# hat.net
KiCad netlist of a schematic drawn in Altium Designer
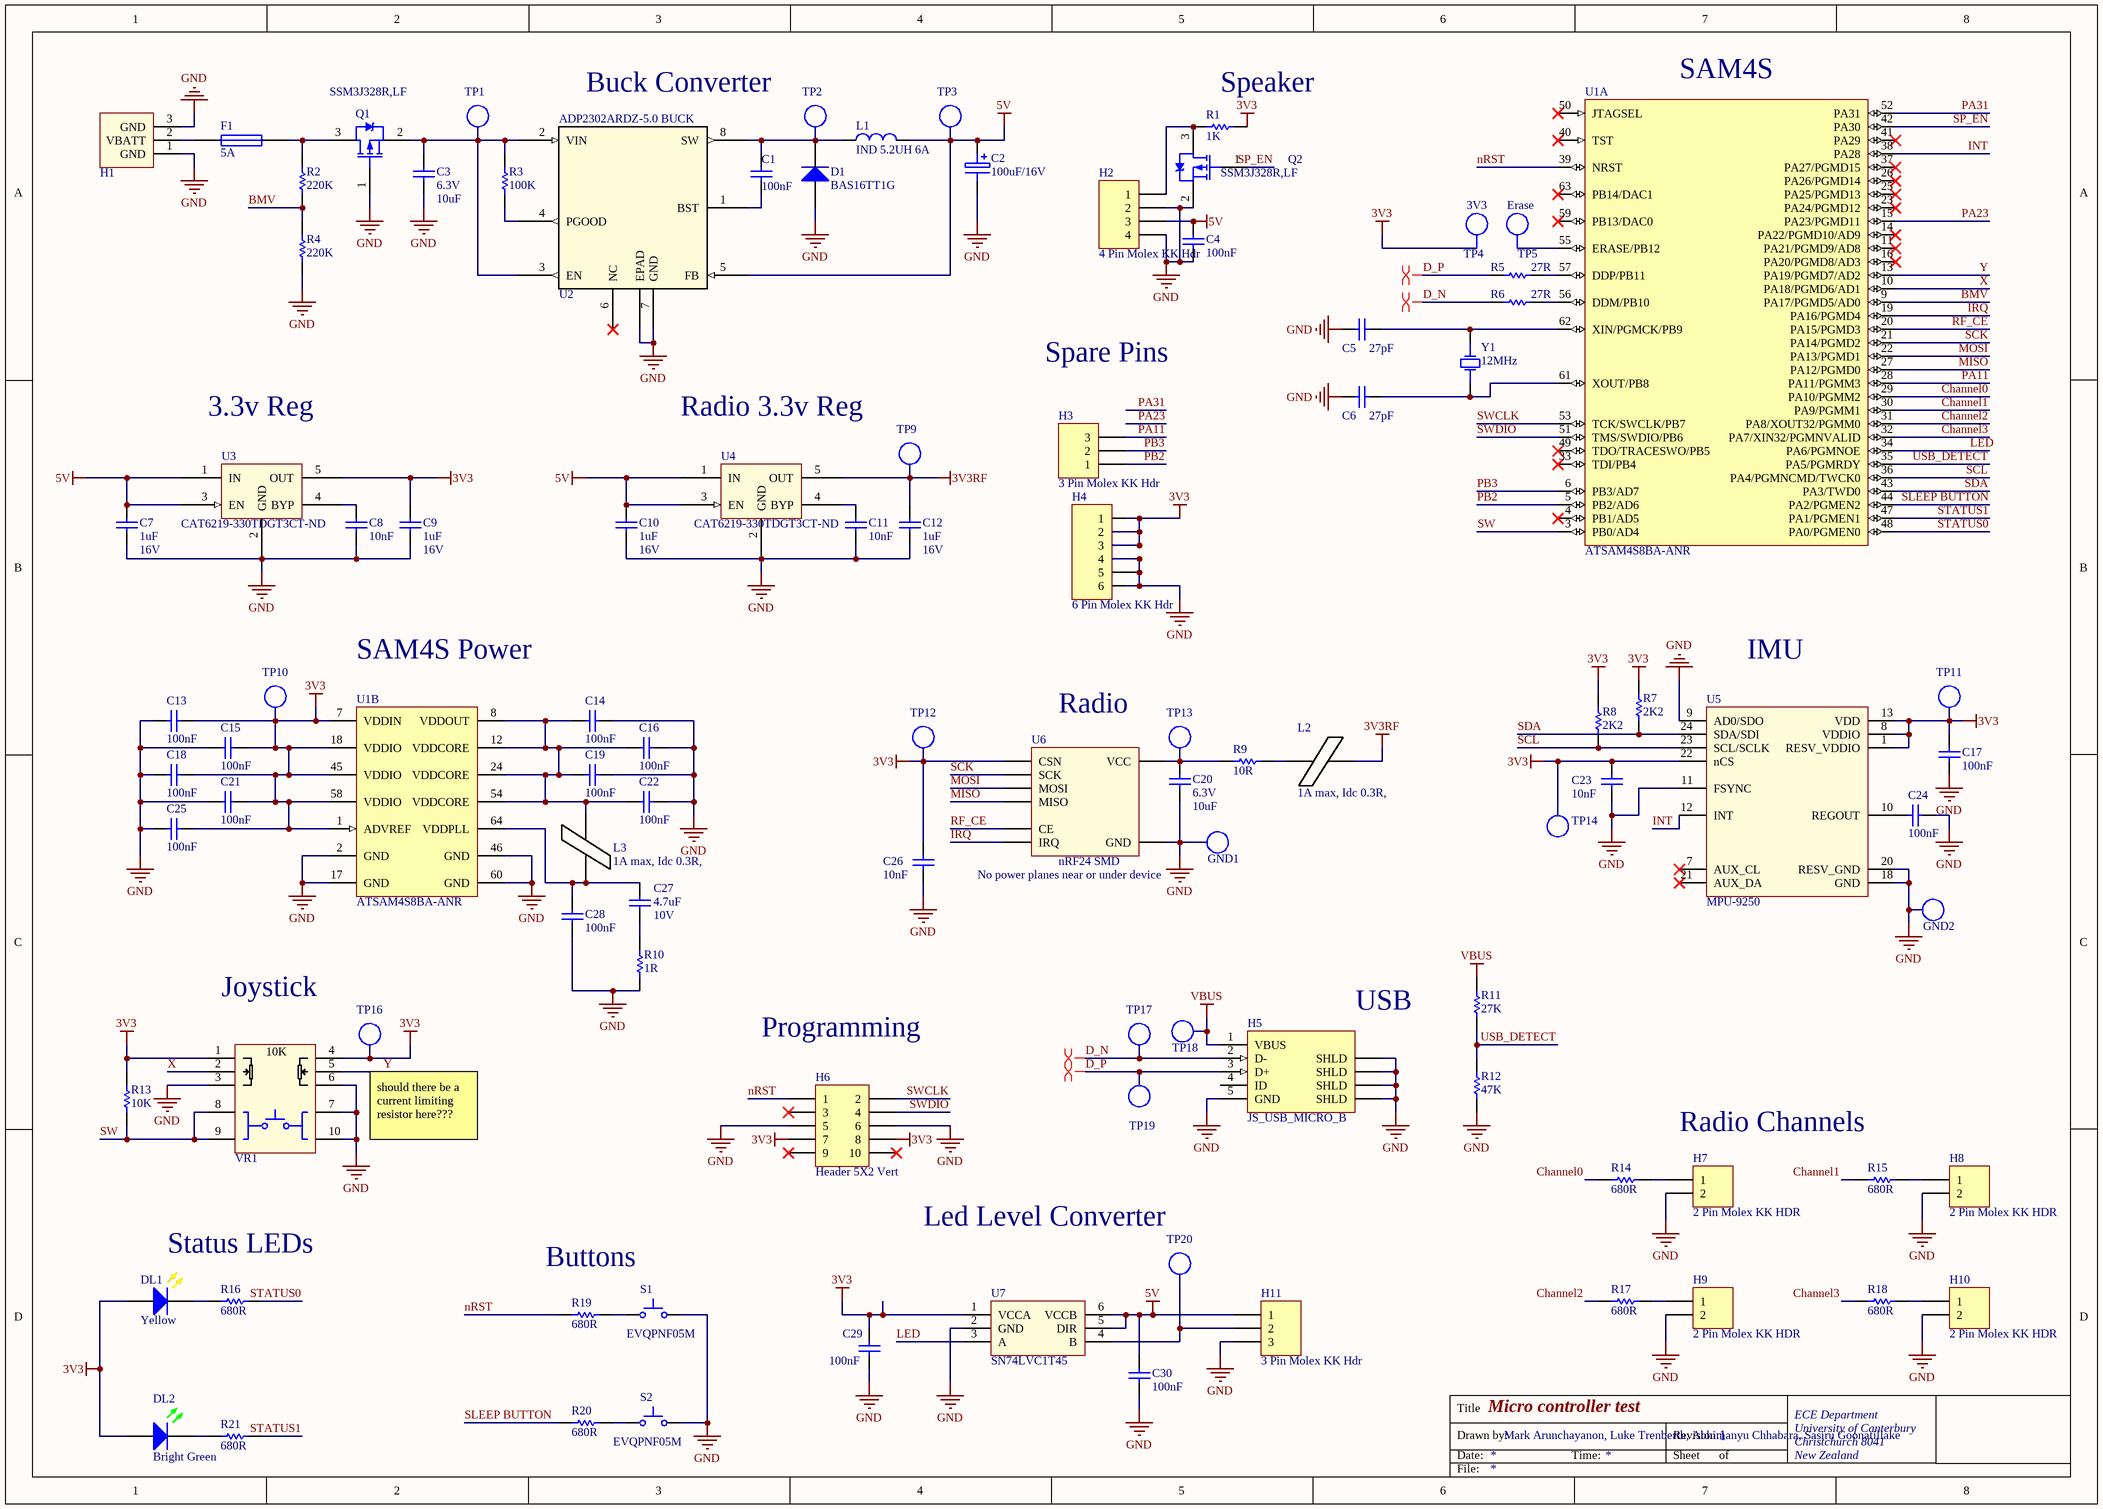
[diagram p0: hat.SchDoc]

(export (version "E")
  (design (tool "Eeschema 10.0.6"))
  (components
    (comp (ref "C1")
      (value "100nF")
      (footprint "CAPC1608L")
      (description "CAP CER 100nF X7R +-10% 50V 0603")
      (libsource (lib "ECE AD19Components_19V1") (part "CC_100nF_0603"))
    )
    (comp (ref "C2")
      (value "100uF/16V")
      (footprint "NICH-1")
      (description "CAP ALUM 100uF 16V SMD")
      (fields (field (name "MANUFACTURER") "Nichcon"))
      (libsource (lib "ECE AD19Components_19V1") (part "CA_100uF_16V"))
    )
    (comp (ref "C3")
      (value "10uF")
      (footprint "CAPC1608L")
      (description "CAP CER 10UF X5R +-20% 6V3 0603")
      (fields (field (name "VOLTAGE - RATED") "6.3V"))
      (libsource (lib "ECE AD19Components_19V1") (part "CC_10uF_0603"))
    )
    (comp (ref "C4")
      (value "100nF")
      (footprint "CAPC1608L")
      (description "CAP CER 100nF X7R +-10% 50V 0603")
      (libsource (lib "ECE AD19Components_19V1") (part "CC_100nF_0603"))
    )
    (comp (ref "C5")
      (value "27pF")
      (footprint "CAPC1608L")
      (description "CAP CER 27pF NPO/COG +-5% 50V 0603")
      (libsource (lib "ECE AD19Components_19V1") (part "CC_27pF_0603"))
    )
    (comp (ref "C6")
      (value "27pF")
      (footprint "CAPC1608L")
      (description "CAP CER 27pF NPO/COG +-5% 50V 0603")
      (libsource (lib "ECE AD19Components_19V1") (part "CC_27pF_0603"))
    )
    (comp (ref "C7")
      (value "1uF")
      (footprint "CAPC1608L")
      (description "CAP CER 1uF Y5V -20% +80% 16V 0603")
      (fields (field (name "MAX VOLTAGE") "16V"))
      (libsource (lib "ECE AD19Components_19V1") (part "CC_1uF_0603"))
    )
    (comp (ref "C8")
      (value "10nF")
      (footprint "CAPC1608L")
      (description "CAP CER 10nF X7R +-10% 50V 0603")
      (libsource (lib "ECE AD19Components_19V1") (part "CC_10nF_0603"))
    )
    (comp (ref "C9")
      (value "1uF")
      (footprint "CAPC1608L")
      (description "CAP CER 1uF Y5V -20% +80% 16V 0603")
      (fields (field (name "MAX VOLTAGE") "16V"))
      (libsource (lib "ECE AD19Components_19V1") (part "CC_1uF_0603"))
    )
    (comp (ref "C10")
      (value "1uF")
      (footprint "CAPC1608L")
      (description "CAP CER 1uF Y5V -20% +80% 16V 0603")
      (fields (field (name "MAX VOLTAGE") "16V"))
      (libsource (lib "ECE AD19Components_19V1") (part "CC_1uF_0603"))
    )
    (comp (ref "C11")
      (value "10nF")
      (footprint "CAPC1608L")
      (description "CAP CER 10nF X7R +-10% 50V 0603")
      (libsource (lib "ECE AD19Components_19V1") (part "CC_10nF_0603"))
    )
    (comp (ref "C12")
      (value "1uF")
      (footprint "CAPC1608L")
      (description "CAP CER 1uF Y5V -20% +80% 16V 0603")
      (fields (field (name "MAX VOLTAGE") "16V"))
      (libsource (lib "ECE AD19Components_19V1") (part "CC_1uF_0603"))
    )
    (comp (ref "C13")
      (value "100nF")
      (footprint "CAPC1608L")
      (description "CAP CER 100nF X7R +-10% 50V 0603")
      (libsource (lib "ECE AD19Components_19V1") (part "CC_100nF_0603"))
    )
    (comp (ref "C14")
      (value "100nF")
      (footprint "CAPC1608L")
      (description "CAP CER 100nF X7R +-10% 50V 0603")
      (libsource (lib "ECE AD19Components_19V1") (part "CC_100nF_0603"))
    )
    (comp (ref "C15")
      (value "100nF")
      (footprint "CAPC1608L")
      (description "CAP CER 100nF X7R +-10% 50V 0603")
      (libsource (lib "ECE AD19Components_19V1") (part "CC_100nF_0603"))
    )
    (comp (ref "C16")
      (value "100nF")
      (footprint "CAPC1608L")
      (description "CAP CER 100nF X7R +-10% 50V 0603")
      (libsource (lib "ECE AD19Components_19V1") (part "CC_100nF_0603"))
    )
    (comp (ref "C17")
      (value "100nF")
      (footprint "CAPC1608L")
      (description "CAP CER 100nF X7R +-10% 50V 0603")
      (libsource (lib "ECE AD19Components_19V1") (part "CC_100nF_0603"))
    )
    (comp (ref "C18")
      (value "100nF")
      (footprint "CAPC1608L")
      (description "CAP CER 100nF X7R +-10% 50V 0603")
      (libsource (lib "ECE AD19Components_19V1") (part "CC_100nF_0603"))
    )
    (comp (ref "C19")
      (value "100nF")
      (footprint "CAPC1608L")
      (description "CAP CER 100nF X7R +-10% 50V 0603")
      (libsource (lib "ECE AD19Components_19V1") (part "CC_100nF_0603"))
    )
    (comp (ref "C20")
      (value "10uF")
      (footprint "CAPC1608L")
      (description "CAP CER 10UF X5R +-20% 6V3 0603")
      (fields (field (name "VOLTAGE - RATED") "6.3V"))
      (libsource (lib "ECE AD19Components_19V1") (part "CC_10uF_0603"))
    )
    (comp (ref "C21")
      (value "100nF")
      (footprint "CAPC1608L")
      (description "CAP CER 100nF X7R +-10% 50V 0603")
      (libsource (lib "ECE AD19Components_19V1") (part "CC_100nF_0603"))
    )
    (comp (ref "C22")
      (value "100nF")
      (footprint "CAPC1608L")
      (description "CAP CER 100nF X7R +-10% 50V 0603")
      (libsource (lib "ECE AD19Components_19V1") (part "CC_100nF_0603"))
    )
    (comp (ref "C23")
      (value "10nF")
      (footprint "CAPC1608L")
      (description "CAP CER 10nF X7R +-10% 50V 0603")
      (libsource (lib "ECE AD19Components_19V1") (part "CC_10nF_0603"))
    )
    (comp (ref "C24")
      (value "100nF")
      (footprint "CAPC1608L")
      (description "CAP CER 100nF X7R +-10% 50V 0603")
      (libsource (lib "ECE AD19Components_19V1") (part "CC_100nF_0603"))
    )
    (comp (ref "C25")
      (value "100nF")
      (footprint "CAPC1608L")
      (description "CAP CER 100nF X7R +-10% 50V 0603")
      (libsource (lib "ECE AD19Components_19V1") (part "CC_100nF_0603"))
    )
    (comp (ref "C26")
      (value "10nF")
      (footprint "CAPC1608L")
      (description "CAP CER 10nF X7R +-10% 50V 0603")
      (libsource (lib "ECE AD19Components_19V1") (part "CC_10nF_0603"))
    )
    (comp (ref "C27")
      (value "4.7uF")
      (footprint "CAPC1608N")
      (description "CAP CER 4.7uF X5R +-20%  10V 0603")
      (fields (field (name "MAX VOLTAGE") "10V"))
      (libsource (lib "ECE AD19Components_19V1") (part "CC_4.7uF_0603"))
    )
    (comp (ref "C28")
      (value "100nF")
      (footprint "CAPC1608L")
      (description "CAP CER 100nF X7R +-10% 50V 0603")
      (libsource (lib "ECE AD19Components_19V1") (part "CC_100nF_0603"))
    )
    (comp (ref "C29")
      (value "100nF")
      (footprint "CAPC1608L")
      (description "CAP CER 100nF X7R +-10% 50V 0603")
      (libsource (lib "ECE AD19Components_19V1") (part "CC_100nF_0603"))
    )
    (comp (ref "C30")
      (value "100nF")
      (footprint "CAPC1608L")
      (description "CAP CER 100nF X7R +-10% 50V 0603")
      (libsource (lib "ECE AD19Components_19V1") (part "CC_100nF_0603"))
    )
    (comp (ref "D1")
      (value "BAS16TT1G")
      (footprint "SOT416")
      (description "Diode Switching, Vr 75V, 200mA, SOT-416")
      (fields (field (name "MANUFACTURER") "ON Semiconductor"))
      (libsource (lib "ECE AD19Components_19V1") (part "DR_BAS16TT1G"))
    )
    (comp (ref "DL1")
      (value "Yellow")
      (footprint "WL-SMCW0603")
      (description "LED Yellow 120mcd 0603 SMD")
      (fields
        (field (name "MANUFACTURER") "WURTH ELEKTRONIK")
        (field (name "MANUFACTURER PART NUMBER") "150060YS75000")
        (field (name "LED COLOUR") "Yellow")
      )
      (libsource (lib "ECE AD19Components_19V1") (part "DL_150060YS75000"))
    )
    (comp (ref "DL2")
      (value "Bright Green")
      (footprint "WL-SMCW0603")
      (description "LED Bright Green 40mcd 0603 SMD")
      (fields
        (field (name "MANUFACTURER") "WURTH ELEKTRONIK")
        (field (name "MANUFACTURER PART NUMBER") "150060VS75000")
        (field (name "LED COLOUR") "Bright Green")
      )
      (libsource (lib "ECE AD19Components_19V1") (part "DL_150060VS75000"))
    )
    (comp (ref "F1")
      (value "5A")
      (footprint "RESC3216N")
      (description "Fuse 5.0A Fast Acting 1206 SMD")
      (fields (field (name "MANUFACTURER PART NUMBER") "C1F5") (field (name "MANUFACTURER") "Bel TRP"))
      (libsource (lib "ECE AD19Components_19V1") (part "FS_Fuse_5.0A"))
    )
    (comp (ref "GND1")
      (value "TP_0603")
      (footprint "TP_0603")
      (description "Test Point 1.65X0.9X1.2mm SMD")
      (fields
        (field (name "MANUFACTURER") "TE Connectivity AMP Connectors")
        (field (name "MANUFACTURER PART NUMBER") "1625854-3")
      )
      (libsource (lib "ECE AD19Components_19V1") (part "TP_0603"))
    )
    (comp (ref "GND2")
      (value "TP_0603")
      (footprint "TP_0603")
      (description "Test Point 1.65X0.9X1.2mm SMD")
      (fields
        (field (name "MANUFACTURER") "TE Connectivity AMP Connectors")
        (field (name "MANUFACTURER PART NUMBER") "1625854-3")
      )
      (libsource (lib "ECE AD19Components_19V1") (part "TP_0603"))
    )
    (comp (ref "H1")
      (value "Battery_HEADER_3pin")
      (footprint "BATT_HEADER_3POS")
      (description "3Pin Header 2.54mm spacing")
      (libsource (lib "ENCE461AD19_19V2") (part "Battery_HEADER_3pin"))
    )
    (comp (ref "H2")
      (value "4 Pin Molex KK Hdr")
      (footprint "MOLEX_KK_4_HDR")
      (description "CONN HEADER 4POS 2.54mm VERT_Thru Hole")
      (fields (field (name "MANUFACTURER") "Molex") (field (name "Comment") "SMD Vert 1.25mm"))
      (libsource (lib "ECE AD19Components_19V1") (part "JA_MOLEX_KK_4POS"))
    )
    (comp (ref "H3")
      (value "3 Pin Molex KK Hdr")
      (footprint "MOLEX_KK_3_HDR")
      (description "CONN HEADER 3POS 2.54mm VERT_Thru Hole")
      (fields (field (name "MANUFACTURER") "Molex"))
      (libsource (lib "") (part "JA_MOLEX_KK_3POS_1"))
    )
    (comp (ref "H4")
      (value "6 Pin Molex KK Hdr")
      (footprint "MOLEX_KK_6_HDR")
      (description "CONN HEADER 6POS 2.54mm VERT_Thru Hole")
      (fields (field (name "Comment") "SMD Vert 1.25mm"))
      (libsource (lib "ECE AD19Components_19V1") (part "JA_MOLEX_KK_6POS"))
    )
    (comp (ref "H5")
      (value "JS_USB_MICRO_B")
      (footprint "FCI_USB_10118194-0001LF")
      (description "CONN USB MICRO B RECPT SMT R/A")
      (fields (field (name "MANUFACTURER") "FCI") (field (name "MANUFACTURER PART NUMBER") "10118194-0001LF"))
      (libsource (lib "ECE AD19Components_19V1") (part "JS_USB_MICRO_B_SMT"))
    )
    (comp (ref "H6")
      (value "Header 5X2 Vert")
      (footprint "IDC2.54-V10D")
      (description "IDC Header, 2,54mm, 10-Pin, Vert")
      (libsource (lib "ECE AD19Components_19V1") (part "JA_HDR_IDC_5X2_VERT"))
    )
    (comp (ref "H7")
      (value "2 Pin Molex KK HDR")
      (footprint "MOLEX_KK_2_HDR")
      (description "CONN HEADER 2POS 2.54mm VERT_Thru Hole")
      (fields (field (name "Comment") "SMD Vert 1.25mm"))
      (libsource (lib "ECE AD19Components_19V1") (part "JA_MOLEX_KK_2POS"))
    )
    (comp (ref "H8")
      (value "2 Pin Molex KK HDR")
      (footprint "MOLEX_KK_2_HDR")
      (description "CONN HEADER 2POS 2.54mm VERT_Thru Hole")
      (fields (field (name "Comment") "SMD Vert 1.25mm"))
      (libsource (lib "ECE AD19Components_19V1") (part "JA_MOLEX_KK_2POS"))
    )
    (comp (ref "H9")
      (value "2 Pin Molex KK HDR")
      (footprint "MOLEX_KK_2_HDR")
      (description "CONN HEADER 2POS 2.54mm VERT_Thru Hole")
      (fields (field (name "Comment") "SMD Vert 1.25mm"))
      (libsource (lib "ECE AD19Components_19V1") (part "JA_MOLEX_KK_2POS"))
    )
    (comp (ref "H10")
      (value "2 Pin Molex KK HDR")
      (footprint "MOLEX_KK_2_HDR")
      (description "CONN HEADER 2POS 2.54mm VERT_Thru Hole")
      (fields (field (name "Comment") "SMD Vert 1.25mm"))
      (libsource (lib "ECE AD19Components_19V1") (part "JA_MOLEX_KK_2POS"))
    )
    (comp (ref "H11")
      (value "3 Pin Molex KK Hdr")
      (footprint "MOLEX_KK_3_HDR")
      (description "CONN HEADER 3POS 2.54mm VERT_Thru Hole")
      (fields (field (name "MANUFACTURER") "Molex") (field (name "Comment") "SMD Vert 1.25mm"))
      (libsource (lib "ECE AD19Components_19V1") (part "JA_MOLEX_KK_3POS"))
    )
    (comp (ref "L1")
      (value "IND 5.2UH 6A")
      (footprint "INDUCTOR5u2")
      (description "FIXED IND 5.2UH 6A 22 MOHM SMD")
      (fields
        (field (name "MANUFACTURER") "Sumida America Components Inc.")
        (field (name "MANUFACTURER PART NUMBER") "CDRH104RNP-5R2NC")
      )
      (libsource (lib "ENCE461AD19_19V2") (part "CDRH104RNP-5R2NC"))
    )
    (comp (ref "L2")
      (value "1A max, Idc 0.3R,")
      (footprint "INDC3216L")
      (description "Ferrite Bead, Rdc 0.3R, Z100MHZ 600R, Imax 1A, SMD 1206")
      (fields
        (field (name "MANUFACTURER") "FAIR-RITE")
        (field (name "MANUFACTURER PART NUMBER") "2512066017Y1")
      )
      (libsource (lib "ECE AD19Components_19V1") (part "IN_Ferrite-Bead"))
    )
    (comp (ref "L3")
      (value "1A max, Idc 0.3R,")
      (footprint "INDC3216L")
      (description "Ferrite Bead, Rdc 0.3R, Z100MHZ 600R, Imax 1A, SMD 1206")
      (fields
        (field (name "MANUFACTURER") "FAIR-RITE")
        (field (name "MANUFACTURER PART NUMBER") "2512066017Y1")
      )
      (libsource (lib "ECE AD19Components_19V1") (part "IN_Ferrite-Bead"))
    )
    (comp (ref "Q1")
      (value "SSM3J328R,LF")
      (footprint "SOT23_L")
      (description "MOSFET P-CH 20V 6A SOT23-3")
      (fields
        (field (name "MANUFACTURER") "Toshiba")
        (field (name "MANUFACTURER PART NUMBER") "SSM3J328R,LF")
      )
      (libsource (lib "ECE AD19Components_19V1") (part "TM_SSM3J328R"))
    )
    (comp (ref "Q2")
      (value "SSM3J328R,LF")
      (footprint "SOT23_L")
      (description "MOSFET P-CH 20V 6A SOT23-3")
      (fields
        (field (name "MANUFACTURER") "Toshiba")
        (field (name "MANUFACTURER PART NUMBER") "SSM3J328R,LF")
      )
      (libsource (lib "ECE AD19Components_19V1") (part "TM_SSM3J328R"))
    )
    (comp (ref "R1")
      (value "1K")
      (footprint "RESC1608L")
      (description "RES 1.0K OHM 1/10W 5% 0603 SMD")
      (libsource (lib "ECE AD19Components_19V1") (part "RS_1K"))
    )
    (comp (ref "R2")
      (value "220K")
      (footprint "RESC1608L")
      (description "RES 3.3K OHM 1/10W 5% 0603 SMD")
      (libsource (lib "ECE AD19Components_19V1") (part "RS_220K"))
    )
    (comp (ref "R3")
      (value "100K")
      (footprint "RESC1608L")
      (description "RES 100K OHM 1/10W 5% 0603 SMD")
      (libsource (lib "ECE AD19Components_19V1") (part "RS_100K"))
    )
    (comp (ref "R4")
      (value "220K")
      (footprint "RESC1608L")
      (description "RES 3.3K OHM 1/10W 5% 0603 SMD")
      (libsource (lib "ECE AD19Components_19V1") (part "RS_220K"))
    )
    (comp (ref "R5")
      (value "27R")
      (footprint "RESC3216L")
      (description "RES 27R OHM 1/4W 5% 1206 SMD")
      (libsource (lib "ECE AD19Components_19V1") (part "RT_27R"))
    )
    (comp (ref "R6")
      (value "27R")
      (footprint "RESC3216L")
      (description "RES 27R OHM 1/4W 5% 1206 SMD")
      (libsource (lib "ECE AD19Components_19V1") (part "RT_27R"))
    )
    (comp (ref "R7")
      (value "2K2")
      (footprint "RESC1608L")
      (description "RES 2.2K OHM 1/10W 5% 0603 SMD")
      (libsource (lib "ECE AD19Components_19V1") (part "RS_2K2"))
    )
    (comp (ref "R8")
      (value "2K2")
      (footprint "RESC1608L")
      (description "RES 2.2K OHM 1/10W 5% 0603 SMD")
      (libsource (lib "ECE AD19Components_19V1") (part "RS_2K2"))
    )
    (comp (ref "R9")
      (value "10R")
      (footprint "RESC1608L")
      (description "RES 10 OHM 1/10W 5% 0603 SMD")
      (libsource (lib "ECE AD19Components_19V1") (part "RS_10R"))
    )
    (comp (ref "R10")
      (value "1R")
      (footprint "RESC3216L")
      (description "RES 1R OHM 1/4W 5% 1206 SMD")
      (libsource (lib "ECE AD19Components_19V1") (part "RT_1R"))
    )
    (comp (ref "R11")
      (value "27K")
      (footprint "RESC1608L")
      (description "RES 27K OHM 1/10W 5% 0603 SMD")
      (libsource (lib "ECE AD19Components_19V1") (part "RS_27K"))
    )
    (comp (ref "R12")
      (value "47K")
      (footprint "RESC1608N")
      (description "RES 47.0K OHM 1/10W 5% 0603 SMD")
      (libsource (lib "ECE AD19Components_19V1") (part "RS_47K"))
    )
    (comp (ref "R13")
      (value "10K")
      (footprint "RESC1608L")
      (description "RES 10.0K OHM 1/10W 5% 0603 SMD")
      (libsource (lib "ECE AD19Components_19V1") (part "RS_10K"))
    )
    (comp (ref "R14")
      (value "680R")
      (footprint "RESC1608L")
      (description "RES 680 OHM 1/10W 5% 0603 SMD")
      (libsource (lib "ECE AD19Components_19V1") (part "RS_680R"))
    )
    (comp (ref "R15")
      (value "680R")
      (footprint "RESC1608L")
      (description "RES 680 OHM 1/10W 5% 0603 SMD")
      (libsource (lib "ECE AD19Components_19V1") (part "RS_680R"))
    )
    (comp (ref "R16")
      (value "680R")
      (footprint "RESC1608L")
      (description "RES 680 OHM 1/10W 5% 0603 SMD")
      (libsource (lib "ECE AD19Components_19V1") (part "RS_680R"))
    )
    (comp (ref "R17")
      (value "680R")
      (footprint "RESC1608L")
      (description "RES 680 OHM 1/10W 5% 0603 SMD")
      (libsource (lib "ECE AD19Components_19V1") (part "RS_680R"))
    )
    (comp (ref "R18")
      (value "680R")
      (footprint "RESC1608L")
      (description "RES 680 OHM 1/10W 5% 0603 SMD")
      (libsource (lib "ECE AD19Components_19V1") (part "RS_680R"))
    )
    (comp (ref "R19")
      (value "680R")
      (footprint "RESC1608L")
      (description "RES 680 OHM 1/10W 5% 0603 SMD")
      (libsource (lib "ECE AD19Components_19V1") (part "RS_680R"))
    )
    (comp (ref "R20")
      (value "680R")
      (footprint "RESC1608L")
      (description "RES 680 OHM 1/10W 5% 0603 SMD")
      (libsource (lib "ECE AD19Components_19V1") (part "RS_680R"))
    )
    (comp (ref "R21")
      (value "680R")
      (footprint "RESC1608L")
      (description "RES 680 OHM 1/10W 5% 0603 SMD")
      (libsource (lib "ECE AD19Components_19V1") (part "RS_680R"))
    )
    (comp (ref "S1")
      (value "EVQPNF05M")
      (footprint "EVQPNF05M")
      (description "Panasonic 6 x 3.5mm SMD Light Touch Switch Type SMD")
      (fields (field (name "MANUFACTURER") "Panasonic"))
      (libsource (lib "ECE AD19Components_19V1") (part "WS_EVQPNF05M"))
    )
    (comp (ref "S2")
      (value "EVQPNF05M")
      (footprint "EVQPNF05M")
      (description "Panasonic 6 x 3.5mm SMD Light Touch Switch Type SMD")
      (fields (field (name "MANUFACTURER") "Panasonic"))
      (libsource (lib "ECE AD19Components_19V1") (part "WS_EVQPNF05M"))
    )
    (comp (ref "TP1")
      (value "TP_0603")
      (footprint "TP_0603")
      (description "Test Point 1.65X0.9X1.2mm SMD")
      (fields
        (field (name "MANUFACTURER") "TE Connectivity AMP Connectors")
        (field (name "MANUFACTURER PART NUMBER") "1625854-3")
      )
      (libsource (lib "ECE AD19Components_19V1") (part "TP_0603"))
    )
    (comp (ref "TP2")
      (value "TP_0603")
      (footprint "TP_0603")
      (description "Test Point 1.65X0.9X1.2mm SMD")
      (fields
        (field (name "MANUFACTURER") "TE Connectivity AMP Connectors")
        (field (name "MANUFACTURER PART NUMBER") "1625854-3")
      )
      (libsource (lib "ECE AD19Components_19V1") (part "TP_0603"))
    )
    (comp (ref "TP3")
      (value "TP_0603")
      (footprint "TP_0603")
      (description "Test Point 1.65X0.9X1.2mm SMD")
      (fields
        (field (name "MANUFACTURER") "TE Connectivity AMP Connectors")
        (field (name "MANUFACTURER PART NUMBER") "1625854-3")
      )
      (libsource (lib "ECE AD19Components_19V1") (part "TP_0603"))
    )
    (comp (ref "TP4")
      (value "3V3")
      (footprint "TP_1206")
      (description "Test-Point 3.3x1.6x2.1mm SMD")
      (fields
        (field (name "MANUFACTURER") "Harwin Inc")
        (field (name "MANUFACTURER PART NUMBER") "S1751-46R")
      )
      (libsource (lib "ECE AD19Components_19V1") (part "TP_1206"))
    )
    (comp (ref "TP5")
      (value "Erase")
      (footprint "TP_1206")
      (description "Test-Point 3.3x1.6x2.1mm SMD")
      (fields
        (field (name "MANUFACTURER") "Harwin Inc")
        (field (name "MANUFACTURER PART NUMBER") "S1751-46R")
      )
      (libsource (lib "ECE AD19Components_19V1") (part "TP_1206"))
    )
    (comp (ref "TP9")
      (value "TP_0603")
      (footprint "TP_0603")
      (description "Test Point 1.65X0.9X1.2mm SMD")
      (fields
        (field (name "MANUFACTURER") "TE Connectivity AMP Connectors")
        (field (name "MANUFACTURER PART NUMBER") "1625854-3")
      )
      (libsource (lib "ECE AD19Components_19V1") (part "TP_0603"))
    )
    (comp (ref "TP10")
      (value "TP_0603")
      (footprint "TP_0603")
      (description "Test Point 1.65X0.9X1.2mm SMD")
      (fields
        (field (name "MANUFACTURER") "TE Connectivity AMP Connectors")
        (field (name "MANUFACTURER PART NUMBER") "1625854-3")
      )
      (libsource (lib "ECE AD19Components_19V1") (part "TP_0603"))
    )
    (comp (ref "TP11")
      (value "TP_0603")
      (footprint "TP_0603")
      (description "Test Point 1.65X0.9X1.2mm SMD")
      (fields
        (field (name "MANUFACTURER") "TE Connectivity AMP Connectors")
        (field (name "MANUFACTURER PART NUMBER") "1625854-3")
      )
      (libsource (lib "ECE AD19Components_19V1") (part "TP_0603"))
    )
    (comp (ref "TP12")
      (value "TP_0603")
      (footprint "TP_0603")
      (description "Test Point 1.65X0.9X1.2mm SMD")
      (fields
        (field (name "MANUFACTURER") "TE Connectivity AMP Connectors")
        (field (name "MANUFACTURER PART NUMBER") "1625854-3")
      )
      (libsource (lib "ECE AD19Components_19V1") (part "TP_0603"))
    )
    (comp (ref "TP13")
      (value "TP_0603")
      (footprint "TP_0603")
      (description "Test Point 1.65X0.9X1.2mm SMD")
      (fields
        (field (name "MANUFACTURER") "TE Connectivity AMP Connectors")
        (field (name "MANUFACTURER PART NUMBER") "1625854-3")
      )
      (libsource (lib "ECE AD19Components_19V1") (part "TP_0603"))
    )
    (comp (ref "TP14")
      (value "TP_0603")
      (footprint "TP_0603")
      (description "Test Point 1.65X0.9X1.2mm SMD")
      (fields
        (field (name "MANUFACTURER") "TE Connectivity AMP Connectors")
        (field (name "MANUFACTURER PART NUMBER") "1625854-3")
      )
      (libsource (lib "ECE AD19Components_19V1") (part "TP_0603"))
    )
    (comp (ref "TP16")
      (value "TP_0603")
      (footprint "TP_0603")
      (description "Test Point 1.65X0.9X1.2mm SMD")
      (fields
        (field (name "MANUFACTURER") "TE Connectivity AMP Connectors")
        (field (name "MANUFACTURER PART NUMBER") "1625854-3")
      )
      (libsource (lib "ECE AD19Components_19V1") (part "TP_0603"))
    )
    (comp (ref "TP17")
      (value "TP_0603")
      (footprint "TP_0603")
      (description "Test Point 1.65X0.9X1.2mm SMD")
      (fields
        (field (name "MANUFACTURER") "TE Connectivity AMP Connectors")
        (field (name "MANUFACTURER PART NUMBER") "1625854-3")
      )
      (libsource (lib "ECE AD19Components_19V1") (part "TP_0603"))
    )
    (comp (ref "TP18")
      (value "TP_0603")
      (footprint "TP_0603")
      (description "Test Point 1.65X0.9X1.2mm SMD")
      (fields
        (field (name "MANUFACTURER") "TE Connectivity AMP Connectors")
        (field (name "MANUFACTURER PART NUMBER") "1625854-3")
      )
      (libsource (lib "ECE AD19Components_19V1") (part "TP_0603"))
    )
    (comp (ref "TP19")
      (value "TP_0603")
      (footprint "TP_0603")
      (description "Test Point 1.65X0.9X1.2mm SMD")
      (fields
        (field (name "MANUFACTURER") "TE Connectivity AMP Connectors")
        (field (name "MANUFACTURER PART NUMBER") "1625854-3")
      )
      (libsource (lib "ECE AD19Components_19V1") (part "TP_0603"))
    )
    (comp (ref "TP20")
      (value "TP_0603")
      (footprint "TP_0603")
      (description "Test Point 1.65X0.9X1.2mm SMD")
      (fields
        (field (name "MANUFACTURER") "TE Connectivity AMP Connectors")
        (field (name "MANUFACTURER PART NUMBER") "1625854-3")
      )
      (libsource (lib "ECE AD19Components_19V1") (part "TP_0603"))
    )
    (comp (ref "U1")
      (value "ATSAM4S8BA-ANR")
      (footprint "LQFP64_L")
      (description "IC MCU 32BIT 512KB FLASH 64LQFP")
      (fields (field (name "MANUFACTURER") "Atmel"))
      (libsource (lib "ECE AD19Components_19V1") (part "SE_ATSAM4S16BA-MU"))
    )
    (comp (ref "U2")
      (value "ADP2302ARDZ-5.0 BUCK")
      (footprint "RD_8_1")
      (description "IC REG BUCK 5V 2A 8SOIC")
      (fields (field (name "MANUFACTURER_PART_NUMBER") "ADP2302ARDZ-5.0-R7"))
      (libsource (lib "ENCE461AD19_19V2") (part "ADP2302ARDZ-5.0-R7"))
    )
    (comp (ref "U3")
      (value "CAT6219-330TDGT3")
      (footprint "SOT95P280X145-5N")
      (description "IC REG LIN 3.3V 500MA TSOT23-5")
      (fields
        (field (name "BASE PART NUMBER") "CAT6219")
        (field (name "SUPPLIER PART NUMBER") "CAT6219-330TDGT3CT-ND")
      )
      (libsource (lib "ENCE461AD19_19V2") (part "SV_CAT6219-330TDGT3"))
    )
    (comp (ref "U4")
      (value "CAT6219-330TDGT3")
      (footprint "SOT95P280X145-5N")
      (description "IC REG LIN 3.3V 500MA TSOT23-5")
      (fields
        (field (name "BASE PART NUMBER") "CAT6219")
        (field (name "SUPPLIER PART NUMBER") "CAT6219-330TDGT3CT-ND")
      )
      (libsource (lib "ENCE461AD19_19V2") (part "SV_CAT6219-330TDGT3"))
    )
    (comp (ref "U5")
      (value "MPU-9250")
      (footprint "Quad24")
      (description "9 axis IMU")
      (libsource (lib "ENCE461AD19_19V2") (part "MPU-9250"))
    )
    (comp (ref "U6")
      (value "nRF24 SMD")
      (footprint "NRF24")
      (description "nRF24 SMD Module")
      (fields (field (name "WARNING") "No power planes near or under device"))
      (libsource (lib "ENCE461AD19_19V2") (part "NRF24"))
    )
    (comp (ref "U7")
      (value "SN74LVC1T45")
      (footprint "SOT23-6_N")
      (description "1.8V - 5V level converter")
      (libsource (lib "ENCE461_extras_2020") (part "SN74LVC1T45"))
    )
    (comp (ref "VR1")
      (value "Joystick 10k with Sw")
      (footprint "Joystick_Sw")
      (description "JOYSTICK 10K OHM 2 AXIS TH")
      (libsource (lib "ENCE461AD19_19V2") (part "Joystick 10k with Sw"))
    )
    (comp (ref "Y1")
      (value "12MHz")
      (footprint "6.0X3.5-4")
      (description "CRYSTAL 12MHZ 18PF 6X3.5mm SMD")
      (fields
        (field (name "MANUFACTURER") "CTS-Frequency Controls")
        (field (name "MANUFACTURER PART NUMBER") "406C35D12M00000")
        (field (name "FREQUENCY") "12MHz")
      )
      (libsource (lib "ECE AD19Components_19V1") (part "XT_CRYSTAL_12MHz_18pF"))
    )
  )
  (nets
    (net (code "1") (name "/BMV") (class "Default")
      (node (ref "R2") (pin "1") (pinfunction "1_1") (pintype "passive"))
      (node (ref "R4") (pin "2") (pinfunction "2_2") (pintype "passive"))
      (node (ref "U1") (pin "9") (pinfunction "PA17/PGMD5/AD0_9") (pintype "bidirectional"))
    )
    (net (code "2") (name "/Channel0") (class "Default")
      (node (ref "R14") (pin "1") (pinfunction "1_1") (pintype "passive"))
      (node (ref "U1") (pin "29") (pinfunction "PA10/PGMM2_29") (pintype "bidirectional"))
    )
    (net (code "3") (name "/Channel1") (class "Default")
      (node (ref "R15") (pin "1") (pinfunction "1_1") (pintype "passive"))
      (node (ref "U1") (pin "30") (pinfunction "PA9/PGMM1_30") (pintype "bidirectional"))
    )
    (net (code "4") (name "/Channel2") (class "Default")
      (node (ref "R17") (pin "1") (pinfunction "1_1") (pintype "passive"))
      (node (ref "U1") (pin "31") (pinfunction "PA8/XOUT32/PGMM0_31") (pintype "bidirectional"))
    )
    (net (code "5") (name "/Channel3") (class "Default")
      (node (ref "R18") (pin "1") (pinfunction "1_1") (pintype "passive"))
      (node (ref "U1") (pin "32") (pinfunction "PA7/XIN32/PGMNVALID_32") (pintype "bidirectional"))
    )
    (net (code "6") (name "/D_N") (class "Default")
      (node (ref "H5") (pin "2") (pinfunction "D-_2") (pintype "input"))
      (node (ref "R6") (pin "1") (pinfunction "1_1") (pintype "passive"))
      (node (ref "TP17") (pin "1") (pinfunction "TP_1") (pintype "passive"))
    )
    (net (code "7") (name "/D_P") (class "Default")
      (node (ref "H5") (pin "3") (pinfunction "D+_3") (pintype "input"))
      (node (ref "R5") (pin "1") (pinfunction "1_1") (pintype "passive"))
      (node (ref "TP19") (pin "1") (pinfunction "TP_1") (pintype "passive"))
    )
    (net (code "8") (name "/INT") (class "Default")
      (node (ref "U1") (pin "38") (pinfunction "PA28_38") (pintype "bidirectional"))
      (node (ref "U5") (pin "12") (pinfunction "INT_12") (pintype "passive"))
    )
    (net (code "9") (name "/IRQ") (class "Default")
      (node (ref "U1") (pin "19") (pinfunction "PA16/PGMD4_19") (pintype "bidirectional"))
      (node (ref "U6") (pin "8") (pinfunction "IRQ_8") (pintype "passive"))
    )
    (net (code "10") (name "/LED") (class "Default")
      (node (ref "U1") (pin "34") (pinfunction "PA6/PGMNOE_34") (pintype "bidirectional"))
      (node (ref "U7") (pin "3") (pinfunction "A_3") (pintype "passive"))
    )
    (net (code "11") (name "/MISO") (class "Default")
      (node (ref "U1") (pin "27") (pinfunction "PA12/PGMD0_27") (pintype "bidirectional"))
      (node (ref "U6") (pin "7") (pinfunction "MISO_7") (pintype "passive"))
    )
    (net (code "12") (name "/MOSI") (class "Default")
      (node (ref "U1") (pin "22") (pinfunction "PA13/PGMD1_22") (pintype "bidirectional"))
      (node (ref "U6") (pin "6") (pinfunction "MOSI_6") (pintype "passive"))
    )
    (net (code "13") (name "/PA11") (class "Default")
      (node (ref "H3") (pin "3") (pinfunction "3_3") (pintype "passive"))
      (node (ref "U1") (pin "28") (pinfunction "PA11/PGMM3_28") (pintype "bidirectional"))
    )
    (net (code "14") (name "/PA23") (class "Default")
      (node (ref "U1") (pin "15") (pinfunction "PA23/PGMD11_15") (pintype "bidirectional"))
    )
    (net (code "15") (name "/PA31") (class "Default")
      (node (ref "U1") (pin "52") (pinfunction "PA31_52") (pintype "bidirectional"))
    )
    (net (code "16") (name "/PB2") (class "Default")
      (node (ref "H3") (pin "1") (pinfunction "1_1") (pintype "passive"))
      (node (ref "U1") (pin "5") (pinfunction "PB2/AD6_5") (pintype "bidirectional"))
    )
    (net (code "17") (name "/PB3") (class "Default")
      (node (ref "H3") (pin "2") (pinfunction "2_2") (pintype "passive"))
      (node (ref "U1") (pin "6") (pinfunction "PB3/AD7_6") (pintype "bidirectional"))
    )
    (net (code "18") (name "/RF_CE") (class "Default")
      (node (ref "U1") (pin "20") (pinfunction "PA15/PGMD3_20") (pintype "bidirectional"))
      (node (ref "U6") (pin "3") (pinfunction "CE_3") (pintype "passive"))
    )
    (net (code "19") (name "/SCK") (class "Default")
      (node (ref "U1") (pin "21") (pinfunction "PA14/PGMD2_21") (pintype "bidirectional"))
      (node (ref "U6") (pin "5") (pinfunction "SCK_5") (pintype "passive"))
    )
    (net (code "20") (name "/SCL") (class "Default")
      (node (ref "R8") (pin "1") (pinfunction "1_1") (pintype "passive"))
      (node (ref "U1") (pin "36") (pinfunction "PA4/PGMNCMD/TWCK0_36") (pintype "bidirectional"))
      (node (ref "U5") (pin "23") (pinfunction "SCL/SCLK_23") (pintype "passive"))
    )
    (net (code "21") (name "/SDA") (class "Default")
      (node (ref "R7") (pin "1") (pinfunction "1_1") (pintype "passive"))
      (node (ref "U1") (pin "43") (pinfunction "PA3/TWD0_43") (pintype "bidirectional"))
      (node (ref "U5") (pin "24") (pinfunction "SDA/SDI_24") (pintype "passive"))
    )
    (net (code "22") (name "/SLEEP BUTTON") (class "Default")
      (node (ref "R20") (pin "1") (pinfunction "1_1") (pintype "passive"))
      (node (ref "U1") (pin "44") (pinfunction "PA2/PGMEN2_44") (pintype "bidirectional"))
    )
    (net (code "23") (name "/SP_EN") (class "Default")
      (node (ref "Q2") (pin "1") (pinfunction "1_1") (pintype "passive"))
      (node (ref "U1") (pin "42") (pinfunction "PA30_42") (pintype "bidirectional"))
    )
    (net (code "24") (name "/STATUS0") (class "Default")
      (node (ref "R16") (pin "2") (pinfunction "2_2") (pintype "passive"))
      (node (ref "U1") (pin "48") (pinfunction "PA0/PGMEN0_48") (pintype "bidirectional"))
    )
    (net (code "25") (name "/STATUS1") (class "Default")
      (node (ref "R21") (pin "2") (pinfunction "2_2") (pintype "passive"))
      (node (ref "U1") (pin "47") (pinfunction "PA1/PGMEN1_47") (pintype "bidirectional"))
    )
    (net (code "26") (name "/SW") (class "Default")
      (node (ref "R13") (pin "1") (pinfunction "1_1") (pintype "passive"))
      (node (ref "U1") (pin "3") (pinfunction "PB0/AD4_3") (pintype "bidirectional"))
      (node (ref "VR1") (pin "8") (pinfunction "8_8") (pintype "passive"))
      (node (ref "VR1") (pin "9") (pinfunction "9_9") (pintype "passive"))
    )
    (net (code "27") (name "/SWCLK") (class "Default")
      (node (ref "H6") (pin "2") (pinfunction "2_2") (pintype "passive"))
      (node (ref "U1") (pin "53") (pinfunction "TCK/SWCLK/PB7_53") (pintype "bidirectional"))
    )
    (net (code "28") (name "/SWDIO") (class "Default")
      (node (ref "H6") (pin "4") (pinfunction "4_4") (pintype "passive"))
      (node (ref "U1") (pin "51") (pinfunction "TMS/SWDIO/PB6_51") (pintype "bidirectional"))
    )
    (net (code "29") (name "/USB_DETECT") (class "Default")
      (node (ref "R11") (pin "1") (pinfunction "1_1") (pintype "passive"))
      (node (ref "R12") (pin "2") (pinfunction "2_2") (pintype "passive"))
      (node (ref "U1") (pin "35") (pinfunction "PA5/PGMRDY_35") (pintype "bidirectional"))
    )
    (net (code "30") (name "/X") (class "Default")
      (node (ref "U1") (pin "10") (pinfunction "PA18/PGMD6/AD1_10") (pintype "bidirectional"))
      (node (ref "VR1") (pin "2") (pinfunction "2_2") (pintype "passive"))
    )
    (net (code "31") (name "/Y") (class "Default")
      (node (ref "U1") (pin "13") (pinfunction "PA19/PGMD7/AD2_13") (pintype "bidirectional"))
      (node (ref "VR1") (pin "5") (pinfunction "2'_5") (pintype "passive"))
    )
    (net (code "32") (name "/nRST") (class "Default")
      (node (ref "H6") (pin "1") (pinfunction "1_1") (pintype "passive"))
      (node (ref "R19") (pin "1") (pinfunction "1_1") (pintype "passive"))
      (node (ref "U1") (pin "39") (pinfunction "NRST_39") (pintype "bidirectional"))
    )
    (net (code "33") (name "3V3") (class "Default")
      (node (ref "C13") (pin "1") (pinfunction "1_1") (pintype "passive"))
      (node (ref "C15") (pin "1") (pinfunction "1_1") (pintype "passive"))
      (node (ref "C17") (pin "2") (pinfunction "2_2") (pintype "passive"))
      (node (ref "C18") (pin "1") (pinfunction "1_1") (pintype "passive"))
      (node (ref "C21") (pin "1") (pinfunction "1_1") (pintype "passive"))
      (node (ref "C23") (pin "2") (pinfunction "2_2") (pintype "passive"))
      (node (ref "C25") (pin "1") (pinfunction "1_1") (pintype "passive"))
      (node (ref "C26") (pin "2") (pinfunction "2_2") (pintype "passive"))
      (node (ref "C29") (pin "1") (pinfunction "1_1") (pintype "passive"))
      (node (ref "C9") (pin "2") (pinfunction "2_2") (pintype "passive"))
      (node (ref "DL1") (pin "2") (pinfunction "A_2") (pintype "passive"))
      (node (ref "DL2") (pin "2") (pinfunction "A_2") (pintype "passive"))
      (node (ref "H4") (pin "1") (pinfunction "1_1") (pintype "passive"))
      (node (ref "H4") (pin "2") (pinfunction "2_2") (pintype "passive"))
      (node (ref "H4") (pin "3") (pinfunction "3_3") (pintype "passive"))
      (node (ref "H6") (pin "7") (pinfunction "7_7") (pintype "passive"))
      (node (ref "H6") (pin "8") (pinfunction "8_8") (pintype "passive"))
      (node (ref "R1") (pin "2") (pinfunction "2_2") (pintype "passive"))
      (node (ref "R13") (pin "2") (pinfunction "2_2") (pintype "passive"))
      (node (ref "R7") (pin "2") (pinfunction "2_2") (pintype "passive"))
      (node (ref "R8") (pin "2") (pinfunction "2_2") (pintype "passive"))
      (node (ref "TP10") (pin "1") (pinfunction "TP_1") (pintype "passive"))
      (node (ref "TP11") (pin "1") (pinfunction "TP_1") (pintype "passive"))
      (node (ref "TP12") (pin "1") (pinfunction "TP_1") (pintype "passive"))
      (node (ref "TP14") (pin "1") (pinfunction "TP_1") (pintype "passive"))
      (node (ref "TP16") (pin "1") (pinfunction "TP_1") (pintype "passive"))
      (node (ref "TP4") (pin "1") (pinfunction "1_1") (pintype "passive"))
      (node (ref "U1") (pin "1") (pinfunction "ADVREF_1") (pintype "input"))
      (node (ref "U1") (pin "18") (pinfunction "VDDIO_18") (pintype "power_in"))
      (node (ref "U1") (pin "45") (pinfunction "VDDIO_45") (pintype "power_in"))
      (node (ref "U1") (pin "58") (pinfunction "VDDIO_58") (pintype "power_in"))
      (node (ref "U1") (pin "7") (pinfunction "VDDIN_7") (pintype "power_in"))
      (node (ref "U3") (pin "5") (pinfunction "OUT_5") (pintype "power_in"))
      (node (ref "U5") (pin "1") (pinfunction "RESV_VDDIO_1") (pintype "passive"))
      (node (ref "U5") (pin "13") (pinfunction "VDD_13") (pintype "passive"))
      (node (ref "U5") (pin "22") (pinfunction "nCS_22") (pintype "passive"))
      (node (ref "U5") (pin "8") (pinfunction "VDDIO_8") (pintype "passive"))
      (node (ref "U6") (pin "4") (pinfunction "CSN_4") (pintype "passive"))
      (node (ref "U7") (pin "1") (pinfunction "VCCA_1") (pintype "passive"))
      (node (ref "VR1") (pin "1") (pinfunction "1_1") (pintype "passive"))
      (node (ref "VR1") (pin "4") (pinfunction "1'_4") (pintype "passive"))
    )
    (net (code "34") (name "3V3RF") (class "Default")
      (node (ref "C12") (pin "2") (pinfunction "2_2") (pintype "passive"))
      (node (ref "L2") (pin "2") (pinfunction "2_2") (pintype "passive"))
      (node (ref "TP9") (pin "1") (pinfunction "TP_1") (pintype "passive"))
      (node (ref "U4") (pin "5") (pinfunction "OUT_5") (pintype "power_in"))
    )
    (net (code "35") (name "5V") (class "Default")
      (node (ref "C10") (pin "2") (pinfunction "2_2") (pintype "passive"))
      (node (ref "C2") (pin "2") (pintype "passive"))
      (node (ref "C30") (pin "1") (pinfunction "1_1") (pintype "passive"))
      (node (ref "C4") (pin "2") (pinfunction "2_2") (pintype "passive"))
      (node (ref "C7") (pin "2") (pinfunction "2_2") (pintype "passive"))
      (node (ref "H11") (pin "1") (pinfunction "1_1") (pintype "passive"))
      (node (ref "H2") (pin "3") (pinfunction "3_3") (pintype "passive"))
      (node (ref "L1") (pin "2") (pintype "passive"))
      (node (ref "TP3") (pin "1") (pinfunction "TP_1") (pintype "passive"))
      (node (ref "U2") (pin "5") (pinfunction "FB_5") (pintype "input"))
      (node (ref "U3") (pin "1") (pinfunction "IN_1") (pintype "power_in"))
      (node (ref "U3") (pin "3") (pinfunction "EN_3") (pintype "input"))
      (node (ref "U4") (pin "1") (pinfunction "IN_1") (pintype "power_in"))
      (node (ref "U4") (pin "3") (pinfunction "EN_3") (pintype "input"))
      (node (ref "U7") (pin "5") (pinfunction "DIR_5") (pintype "passive"))
      (node (ref "U7") (pin "6") (pinfunction "VCCB_6") (pintype "passive"))
    )
    (net (code "36") (name "GND") (class "Default")
      (node (ref "C10") (pin "1") (pinfunction "1_1") (pintype "passive"))
      (node (ref "C11") (pin "1") (pinfunction "1_1") (pintype "passive"))
      (node (ref "C12") (pin "1") (pinfunction "1_1") (pintype "passive"))
      (node (ref "C13") (pin "2") (pinfunction "2_2") (pintype "passive"))
      (node (ref "C14") (pin "1") (pinfunction "1_1") (pintype "passive"))
      (node (ref "C15") (pin "2") (pinfunction "2_2") (pintype "passive"))
      (node (ref "C16") (pin "1") (pinfunction "1_1") (pintype "passive"))
      (node (ref "C17") (pin "1") (pinfunction "1_1") (pintype "passive"))
      (node (ref "C18") (pin "2") (pinfunction "2_2") (pintype "passive"))
      (node (ref "C19") (pin "1") (pinfunction "1_1") (pintype "passive"))
      (node (ref "C2") (pin "1") (pintype "passive"))
      (node (ref "C20") (pin "1") (pinfunction "1_1") (pintype "passive"))
      (node (ref "C21") (pin "2") (pinfunction "2_2") (pintype "passive"))
      (node (ref "C22") (pin "1") (pinfunction "1_1") (pintype "passive"))
      (node (ref "C23") (pin "1") (pinfunction "1_1") (pintype "passive"))
      (node (ref "C24") (pin "1") (pinfunction "1_1") (pintype "passive"))
      (node (ref "C25") (pin "2") (pinfunction "2_2") (pintype "passive"))
      (node (ref "C26") (pin "1") (pinfunction "1_1") (pintype "passive"))
      (node (ref "C28") (pin "2") (pinfunction "2_2") (pintype "passive"))
      (node (ref "C29") (pin "2") (pinfunction "2_2") (pintype "passive"))
      (node (ref "C3") (pin "1") (pinfunction "1_1") (pintype "passive"))
      (node (ref "C30") (pin "2") (pinfunction "2_2") (pintype "passive"))
      (node (ref "C4") (pin "1") (pinfunction "1_1") (pintype "passive"))
      (node (ref "C5") (pin "1") (pinfunction "1_1") (pintype "passive"))
      (node (ref "C6") (pin "1") (pinfunction "1_1") (pintype "passive"))
      (node (ref "C7") (pin "1") (pinfunction "1_1") (pintype "passive"))
      (node (ref "C8") (pin "1") (pinfunction "1_1") (pintype "passive"))
      (node (ref "C9") (pin "1") (pinfunction "1_1") (pintype "passive"))
      (node (ref "D1") (pin "1") (pinfunction "A_1") (pintype "passive"))
      (node (ref "GND1") (pin "1") (pinfunction "TP_1") (pintype "passive"))
      (node (ref "GND2") (pin "1") (pinfunction "TP_1") (pintype "passive"))
      (node (ref "H1") (pin "1") (pinfunction "GND_1") (pintype "passive"))
      (node (ref "H1") (pin "3") (pinfunction "GND_3") (pintype "passive"))
      (node (ref "H10") (pin "2") (pinfunction "2_2") (pintype "passive"))
      (node (ref "H11") (pin "3") (pinfunction "3_3") (pintype "passive"))
      (node (ref "H2") (pin "2") (pinfunction "2_2") (pintype "passive"))
      (node (ref "H2") (pin "4") (pinfunction "4_4") (pintype "passive"))
      (node (ref "H4") (pin "4") (pinfunction "4_4") (pintype "passive"))
      (node (ref "H4") (pin "5") (pinfunction "5_5") (pintype "passive"))
      (node (ref "H4") (pin "6") (pinfunction "6_6") (pintype "passive"))
      (node (ref "H5") (pin "5") (pinfunction "GND_5") (pintype "passive"))
      (node (ref "H5") (pin "6") (pinfunction "SHLD_6") (pintype "passive"))
      (node (ref "H6") (pin "5") (pinfunction "5_5") (pintype "passive"))
      (node (ref "H6") (pin "6") (pinfunction "6_6") (pintype "passive"))
      (node (ref "H7") (pin "2") (pinfunction "2_2") (pintype "passive"))
      (node (ref "H8") (pin "2") (pinfunction "2_2") (pintype "passive"))
      (node (ref "H9") (pin "2") (pinfunction "2_2") (pintype "passive"))
      (node (ref "Q1") (pin "1") (pinfunction "1_1") (pintype "passive"))
      (node (ref "Q2") (pin "2") (pinfunction "2_2") (pintype "passive"))
      (node (ref "R10") (pin "1") (pinfunction "1_1") (pintype "passive"))
      (node (ref "R12") (pin "1") (pinfunction "1_1") (pintype "passive"))
      (node (ref "R4") (pin "1") (pinfunction "1_1") (pintype "passive"))
      (node (ref "S1") (pin "2") (pintype "passive"))
      (node (ref "S2") (pin "2") (pintype "passive"))
      (node (ref "U1") (pin "17") (pinfunction "GND_17") (pintype "power_in"))
      (node (ref "U1") (pin "2") (pinfunction "GND_2") (pintype "power_in"))
      (node (ref "U1") (pin "46") (pinfunction "GND_46") (pintype "power_in"))
      (node (ref "U1") (pin "60") (pinfunction "GND_60") (pintype "power_in"))
      (node (ref "U2") (pin "7") (pinfunction "GND_7") (pintype "power_in"))
      (node (ref "U2") (pin "EPAD") (pinfunction "EPAD_EPAD") (pintype "passive"))
      (node (ref "U3") (pin "2") (pinfunction "GND_2") (pintype "power_in"))
      (node (ref "U4") (pin "2") (pinfunction "GND_2") (pintype "power_in"))
      (node (ref "U5") (pin "11") (pinfunction "FSYNC_11") (pintype "passive"))
      (node (ref "U5") (pin "18") (pinfunction "GND_18") (pintype "passive"))
      (node (ref "U5") (pin "20") (pinfunction "RESV_GND_20") (pintype "passive"))
      (node (ref "U5") (pin "9") (pinfunction "AD0/SDO_9") (pintype "passive"))
      (node (ref "U6") (pin "2") (pinfunction "GND_2") (pintype "passive"))
      (node (ref "U7") (pin "2") (pinfunction "GND_2") (pintype "passive"))
      (node (ref "VR1") (pin "10") (pinfunction "10_10") (pintype "passive"))
      (node (ref "VR1") (pin "3") (pinfunction "3_3") (pintype "passive"))
      (node (ref "VR1") (pin "6") (pinfunction "3'_6") (pintype "passive"))
      (node (ref "VR1") (pin "7") (pinfunction "7_7") (pintype "passive"))
    )
    (net (code "37") (name "Net-(C27-Pad1)") (class "Default")
      (node (ref "C27") (pin "1") (pinfunction "1_1") (pintype "passive"))
      (node (ref "R10") (pin "2") (pinfunction "2_2") (pintype "passive"))
    )
    (net (code "38") (name "Net-(D1-K)") (class "Default")
      (node (ref "C1") (pin "1") (pinfunction "1_1") (pintype "passive"))
      (node (ref "D1") (pin "3") (pinfunction "K_3") (pintype "passive"))
      (node (ref "L1") (pin "1") (pintype "passive"))
      (node (ref "TP2") (pin "1") (pinfunction "TP_1") (pintype "passive"))
      (node (ref "U2") (pin "8") (pinfunction "SW_8") (pintype "output"))
    )
    (net (code "39") (name "Net-(DL1-K)") (class "Default")
      (node (ref "DL1") (pin "1") (pinfunction "K_1") (pintype "passive"))
      (node (ref "R16") (pin "1") (pinfunction "1_1") (pintype "passive"))
    )
    (net (code "40") (name "Net-(DL2-K)") (class "Default")
      (node (ref "DL2") (pin "1") (pinfunction "K_1") (pintype "passive"))
      (node (ref "R21") (pin "1") (pinfunction "1_1") (pintype "passive"))
    )
    (net (code "41") (name "Net-(F1-Pad2)") (class "Default")
      (node (ref "F1") (pin "2") (pinfunction "2_2") (pintype "passive"))
      (node (ref "Q1") (pin "3") (pinfunction "3_3") (pintype "passive"))
      (node (ref "R2") (pin "2") (pinfunction "2_2") (pintype "passive"))
    )
    (net (code "42") (name "Net-(H1-VBATT)") (class "Default")
      (node (ref "F1") (pin "1") (pinfunction "1_1") (pintype "passive"))
      (node (ref "H1") (pin "2") (pinfunction "VBATT_2") (pintype "passive"))
    )
    (net (code "43") (name "Net-(H2-Pad1)") (class "Default")
      (node (ref "H2") (pin "1") (pinfunction "1_1") (pintype "passive"))
      (node (ref "Q2") (pin "3") (pinfunction "3_3") (pintype "passive"))
      (node (ref "R1") (pin "1") (pinfunction "1_1") (pintype "passive"))
    )
    (net (code "44") (name "Net-(H7-Pad1)") (class "Default")
      (node (ref "H7") (pin "1") (pinfunction "1_1") (pintype "passive"))
      (node (ref "R14") (pin "2") (pinfunction "2_2") (pintype "passive"))
    )
    (net (code "45") (name "Net-(H8-Pad1)") (class "Default")
      (node (ref "H8") (pin "1") (pinfunction "1_1") (pintype "passive"))
      (node (ref "R15") (pin "2") (pinfunction "2_2") (pintype "passive"))
    )
    (net (code "46") (name "Net-(H9-Pad1)") (class "Default")
      (node (ref "H9") (pin "1") (pinfunction "1_1") (pintype "passive"))
      (node (ref "R17") (pin "2") (pinfunction "2_2") (pintype "passive"))
    )
    (net (code "47") (name "Net-(H10-Pad1)") (class "Default")
      (node (ref "H10") (pin "1") (pinfunction "1_1") (pintype "passive"))
      (node (ref "R18") (pin "2") (pinfunction "2_2") (pintype "passive"))
    )
    (net (code "48") (name "Net-(L2-Pad1)") (class "Default")
      (node (ref "L2") (pin "1") (pinfunction "1_1") (pintype "passive"))
      (node (ref "R9") (pin "2") (pinfunction "2_2") (pintype "passive"))
    )
    (net (code "49") (name "Net-(R19-Pad2)") (class "Default")
      (node (ref "R19") (pin "2") (pinfunction "2_2") (pintype "passive"))
      (node (ref "S1") (pin "1") (pintype "passive"))
    )
    (net (code "50") (name "Net-(R20-Pad2)") (class "Default")
      (node (ref "R20") (pin "2") (pinfunction "2_2") (pintype "passive"))
      (node (ref "S2") (pin "1") (pintype "passive"))
    )
    (net (code "51") (name "Net-(TP1-TP)") (class "Default")
      (node (ref "C3") (pin "2") (pinfunction "2_2") (pintype "passive"))
      (node (ref "Q1") (pin "2") (pinfunction "2_2") (pintype "passive"))
      (node (ref "R3") (pin "2") (pinfunction "2_2") (pintype "passive"))
      (node (ref "TP1") (pin "1") (pinfunction "TP_1") (pintype "passive"))
      (node (ref "U2") (pin "2") (pinfunction "VIN_2") (pintype "input"))
      (node (ref "U2") (pin "3") (pinfunction "EN_3") (pintype "output"))
    )
    (net (code "52") (name "Net-(TP13-TP)") (class "Default")
      (node (ref "C20") (pin "2") (pinfunction "2_2") (pintype "passive"))
      (node (ref "R9") (pin "1") (pinfunction "1_1") (pintype "passive"))
      (node (ref "TP13") (pin "1") (pinfunction "TP_1") (pintype "passive"))
      (node (ref "U6") (pin "1") (pinfunction "VCC_1") (pintype "passive"))
    )
    (net (code "53") (name "Net-(TP20-TP)") (class "Default")
      (node (ref "H11") (pin "2") (pinfunction "2_2") (pintype "passive"))
      (node (ref "TP20") (pin "1") (pinfunction "TP_1") (pintype "passive"))
      (node (ref "U7") (pin "4") (pinfunction "B_4") (pintype "passive"))
    )
    (net (code "54") (name "Net-(U1A-DDM{slash}PB10)") (class "Default")
      (node (ref "R6") (pin "2") (pinfunction "2_2") (pintype "passive"))
      (node (ref "U1") (pin "56") (pinfunction "DDM/PB10_56") (pintype "bidirectional"))
    )
    (net (code "55") (name "Net-(U1A-DDP{slash}PB11)") (class "Default")
      (node (ref "R5") (pin "2") (pinfunction "2_2") (pintype "passive"))
      (node (ref "U1") (pin "57") (pinfunction "DDP/PB11_57") (pintype "bidirectional"))
    )
    (net (code "56") (name "Net-(U1A-ERASE{slash}PB12)") (class "Default")
      (node (ref "TP5") (pin "1") (pinfunction "1_1") (pintype "passive"))
      (node (ref "U1") (pin "55") (pinfunction "ERASE/PB12_55") (pintype "bidirectional"))
    )
    (net (code "57") (name "Net-(U1A-XIN{slash}PGMCK{slash}PB9)") (class "Default")
      (node (ref "C5") (pin "2") (pinfunction "2_2") (pintype "passive"))
      (node (ref "U1") (pin "62") (pinfunction "XIN/PGMCK/PB9_62") (pintype "bidirectional"))
      (node (ref "Y1") (pin "3") (pinfunction "OSC2_3") (pintype "passive"))
    )
    (net (code "58") (name "Net-(U1A-XOUT{slash}PB8)") (class "Default")
      (node (ref "C6") (pin "2") (pinfunction "2_2") (pintype "passive"))
      (node (ref "U1") (pin "61") (pinfunction "XOUT/PB8_61") (pintype "bidirectional"))
      (node (ref "Y1") (pin "1") (pinfunction "OSC1_1") (pintype "passive"))
    )
    (net (code "59") (name "Net-(U1B-VDDOUT)") (class "Default")
      (node (ref "C14") (pin "2") (pinfunction "2_2") (pintype "passive"))
      (node (ref "C16") (pin "2") (pinfunction "2_2") (pintype "passive"))
      (node (ref "C19") (pin "2") (pinfunction "2_2") (pintype "passive"))
      (node (ref "C22") (pin "2") (pinfunction "2_2") (pintype "passive"))
      (node (ref "L3") (pin "2") (pinfunction "2_2") (pintype "passive"))
      (node (ref "U1") (pin "12") (pinfunction "VDDCORE_12") (pintype "power_in"))
      (node (ref "U1") (pin "24") (pinfunction "VDDCORE_24") (pintype "power_in"))
      (node (ref "U1") (pin "54") (pinfunction "VDDCORE_54") (pintype "power_in"))
      (node (ref "U1") (pin "8") (pinfunction "VDDOUT_8") (pintype "power_in"))
    )
    (net (code "60") (name "Net-(U1B-VDDPLL)") (class "Default")
      (node (ref "C27") (pin "2") (pinfunction "2_2") (pintype "passive"))
      (node (ref "C28") (pin "1") (pinfunction "1_1") (pintype "passive"))
      (node (ref "L3") (pin "1") (pinfunction "1_1") (pintype "passive"))
      (node (ref "U1") (pin "64") (pinfunction "VDDPLL_64") (pintype "power_in"))
    )
    (net (code "61") (name "Net-(U2-BST)") (class "Default")
      (node (ref "C1") (pin "2") (pinfunction "2_2") (pintype "passive"))
      (node (ref "U2") (pin "1") (pinfunction "BST_1") (pintype "passive"))
    )
    (net (code "62") (name "Net-(U2-PGOOD)") (class "Default")
      (node (ref "R3") (pin "1") (pinfunction "1_1") (pintype "passive"))
      (node (ref "U2") (pin "4") (pinfunction "PGOOD_4") (pintype "output"))
    )
    (net (code "63") (name "Net-(U3-BYP)") (class "Default")
      (node (ref "C8") (pin "2") (pinfunction "2_2") (pintype "passive"))
      (node (ref "U3") (pin "4") (pinfunction "BYP_4") (pintype "passive"))
    )
    (net (code "64") (name "Net-(U4-BYP)") (class "Default")
      (node (ref "C11") (pin "2") (pinfunction "2_2") (pintype "passive"))
      (node (ref "U4") (pin "4") (pinfunction "BYP_4") (pintype "passive"))
    )
    (net (code "65") (name "Net-(U5-REGOUT)") (class "Default")
      (node (ref "C24") (pin "2") (pinfunction "2_2") (pintype "passive"))
      (node (ref "U5") (pin "10") (pinfunction "REGOUT_10") (pintype "passive"))
    )
    (net (code "66") (name "VBUS") (class "Default")
      (node (ref "H5") (pin "1") (pinfunction "VBUS_1") (pintype "power_in"))
      (node (ref "R11") (pin "2") (pinfunction "2_2") (pintype "passive"))
      (node (ref "TP18") (pin "1") (pinfunction "TP_1") (pintype "passive"))
    )
    (net (code "67") (name "unconnected-(H5-ID-Pad4)") (class "Default")
      (node (ref "H5") (pin "4") (pinfunction "ID_4") (pintype "power_in"))
    )
    (net (code "68") (name "unconnected-(H6-Pad3)") (class "Default")
      (node (ref "H6") (pin "3") (pinfunction "3_3") (pintype "passive+no_connect"))
    )
    (net (code "69") (name "unconnected-(H6-Pad9)") (class "Default")
      (node (ref "H6") (pin "9") (pinfunction "9_9") (pintype "passive+no_connect"))
    )
    (net (code "70") (name "unconnected-(H6-Pad10)") (class "Default")
      (node (ref "H6") (pin "10") (pinfunction "10_10") (pintype "passive+no_connect"))
    )
    (net (code "71") (name "unconnected-(U1A-JTAGSEL-Pad50)") (class "Default")
      (node (ref "U1") (pin "50") (pinfunction "JTAGSEL_50") (pintype "input+no_connect"))
    )
    (net (code "72") (name "unconnected-(U1A-PA20{slash}PGMD8{slash}AD3-Pad16)") (class "Default")
      (node (ref "U1") (pin "16") (pinfunction "PA20/PGMD8/AD3_16") (pintype "bidirectional+no_connect"))
    )
    (net (code "73") (name "unconnected-(U1A-PA21{slash}PGMD9{slash}AD8-Pad11)") (class "Default")
      (node (ref "U1") (pin "11") (pinfunction "PA21/PGMD9/AD8_11") (pintype "bidirectional+no_connect"))
    )
    (net (code "74") (name "unconnected-(U1A-PA22{slash}PGMD10{slash}AD9-Pad14)") (class "Default")
      (node (ref "U1") (pin "14") (pinfunction "PA22/PGMD10/AD9_14") (pintype "bidirectional+no_connect"))
    )
    (net (code "75") (name "unconnected-(U1A-PA24{slash}PGMD12-Pad23)") (class "Default")
      (node (ref "U1") (pin "23") (pinfunction "PA24/PGMD12_23") (pintype "bidirectional+no_connect"))
    )
    (net (code "76") (name "unconnected-(U1A-PA25{slash}PGMD13-Pad25)") (class "Default")
      (node (ref "U1") (pin "25") (pinfunction "PA25/PGMD13_25") (pintype "bidirectional+no_connect"))
    )
    (net (code "77") (name "unconnected-(U1A-PA26{slash}PGMD14-Pad26)") (class "Default")
      (node (ref "U1") (pin "26") (pinfunction "PA26/PGMD14_26") (pintype "bidirectional+no_connect"))
    )
    (net (code "78") (name "unconnected-(U1A-PA27{slash}PGMD15-Pad37)") (class "Default")
      (node (ref "U1") (pin "37") (pinfunction "PA27/PGMD15_37") (pintype "bidirectional+no_connect"))
    )
    (net (code "79") (name "unconnected-(U1A-PA29-Pad41)") (class "Default")
      (node (ref "U1") (pin "41") (pinfunction "PA29_41") (pintype "bidirectional+no_connect"))
    )
    (net (code "80") (name "unconnected-(U1A-PB1{slash}AD5-Pad4)") (class "Default")
      (node (ref "U1") (pin "4") (pinfunction "PB1/AD5_4") (pintype "bidirectional+no_connect"))
    )
    (net (code "81") (name "unconnected-(U1A-PB13{slash}DAC0-Pad59)") (class "Default")
      (node (ref "U1") (pin "59") (pinfunction "PB13/DAC0_59") (pintype "bidirectional+no_connect"))
    )
    (net (code "82") (name "unconnected-(U1A-PB14{slash}DAC1-Pad63)") (class "Default")
      (node (ref "U1") (pin "63") (pinfunction "PB14/DAC1_63") (pintype "bidirectional+no_connect"))
    )
    (net (code "83") (name "unconnected-(U1A-TDI{slash}PB4-Pad33)") (class "Default")
      (node (ref "U1") (pin "33") (pinfunction "TDI/PB4_33") (pintype "bidirectional+no_connect"))
    )
    (net (code "84") (name "unconnected-(U1A-TDO{slash}TRACESWO{slash}PB5-Pad49)") (class "Default")
      (node (ref "U1") (pin "49") (pinfunction "TDO/TRACESWO/PB5_49") (pintype "bidirectional+no_connect"))
    )
    (net (code "85") (name "unconnected-(U1A-TST-Pad40)") (class "Default")
      (node (ref "U1") (pin "40") (pinfunction "TST_40") (pintype "input+no_connect"))
    )
    (net (code "86") (name "unconnected-(U2-NC-Pad6)") (class "Default")
      (node (ref "U2") (pin "6") (pinfunction "NC_6") (pintype "passive+no_connect"))
    )
    (net (code "87") (name "unconnected-(U5-AUX_CL-Pad7)") (class "Default")
      (node (ref "U5") (pin "7") (pinfunction "AUX_CL_7") (pintype "passive+no_connect"))
    )
    (net (code "88") (name "unconnected-(U5-AUX_DA-Pad21)") (class "Default")
      (node (ref "U5") (pin "21") (pinfunction "AUX_DA_21") (pintype "passive+no_connect"))
    )
  )
)
